# 401_FramePWR.net
KiCad netlist of a schematic drawn in Altium Designer
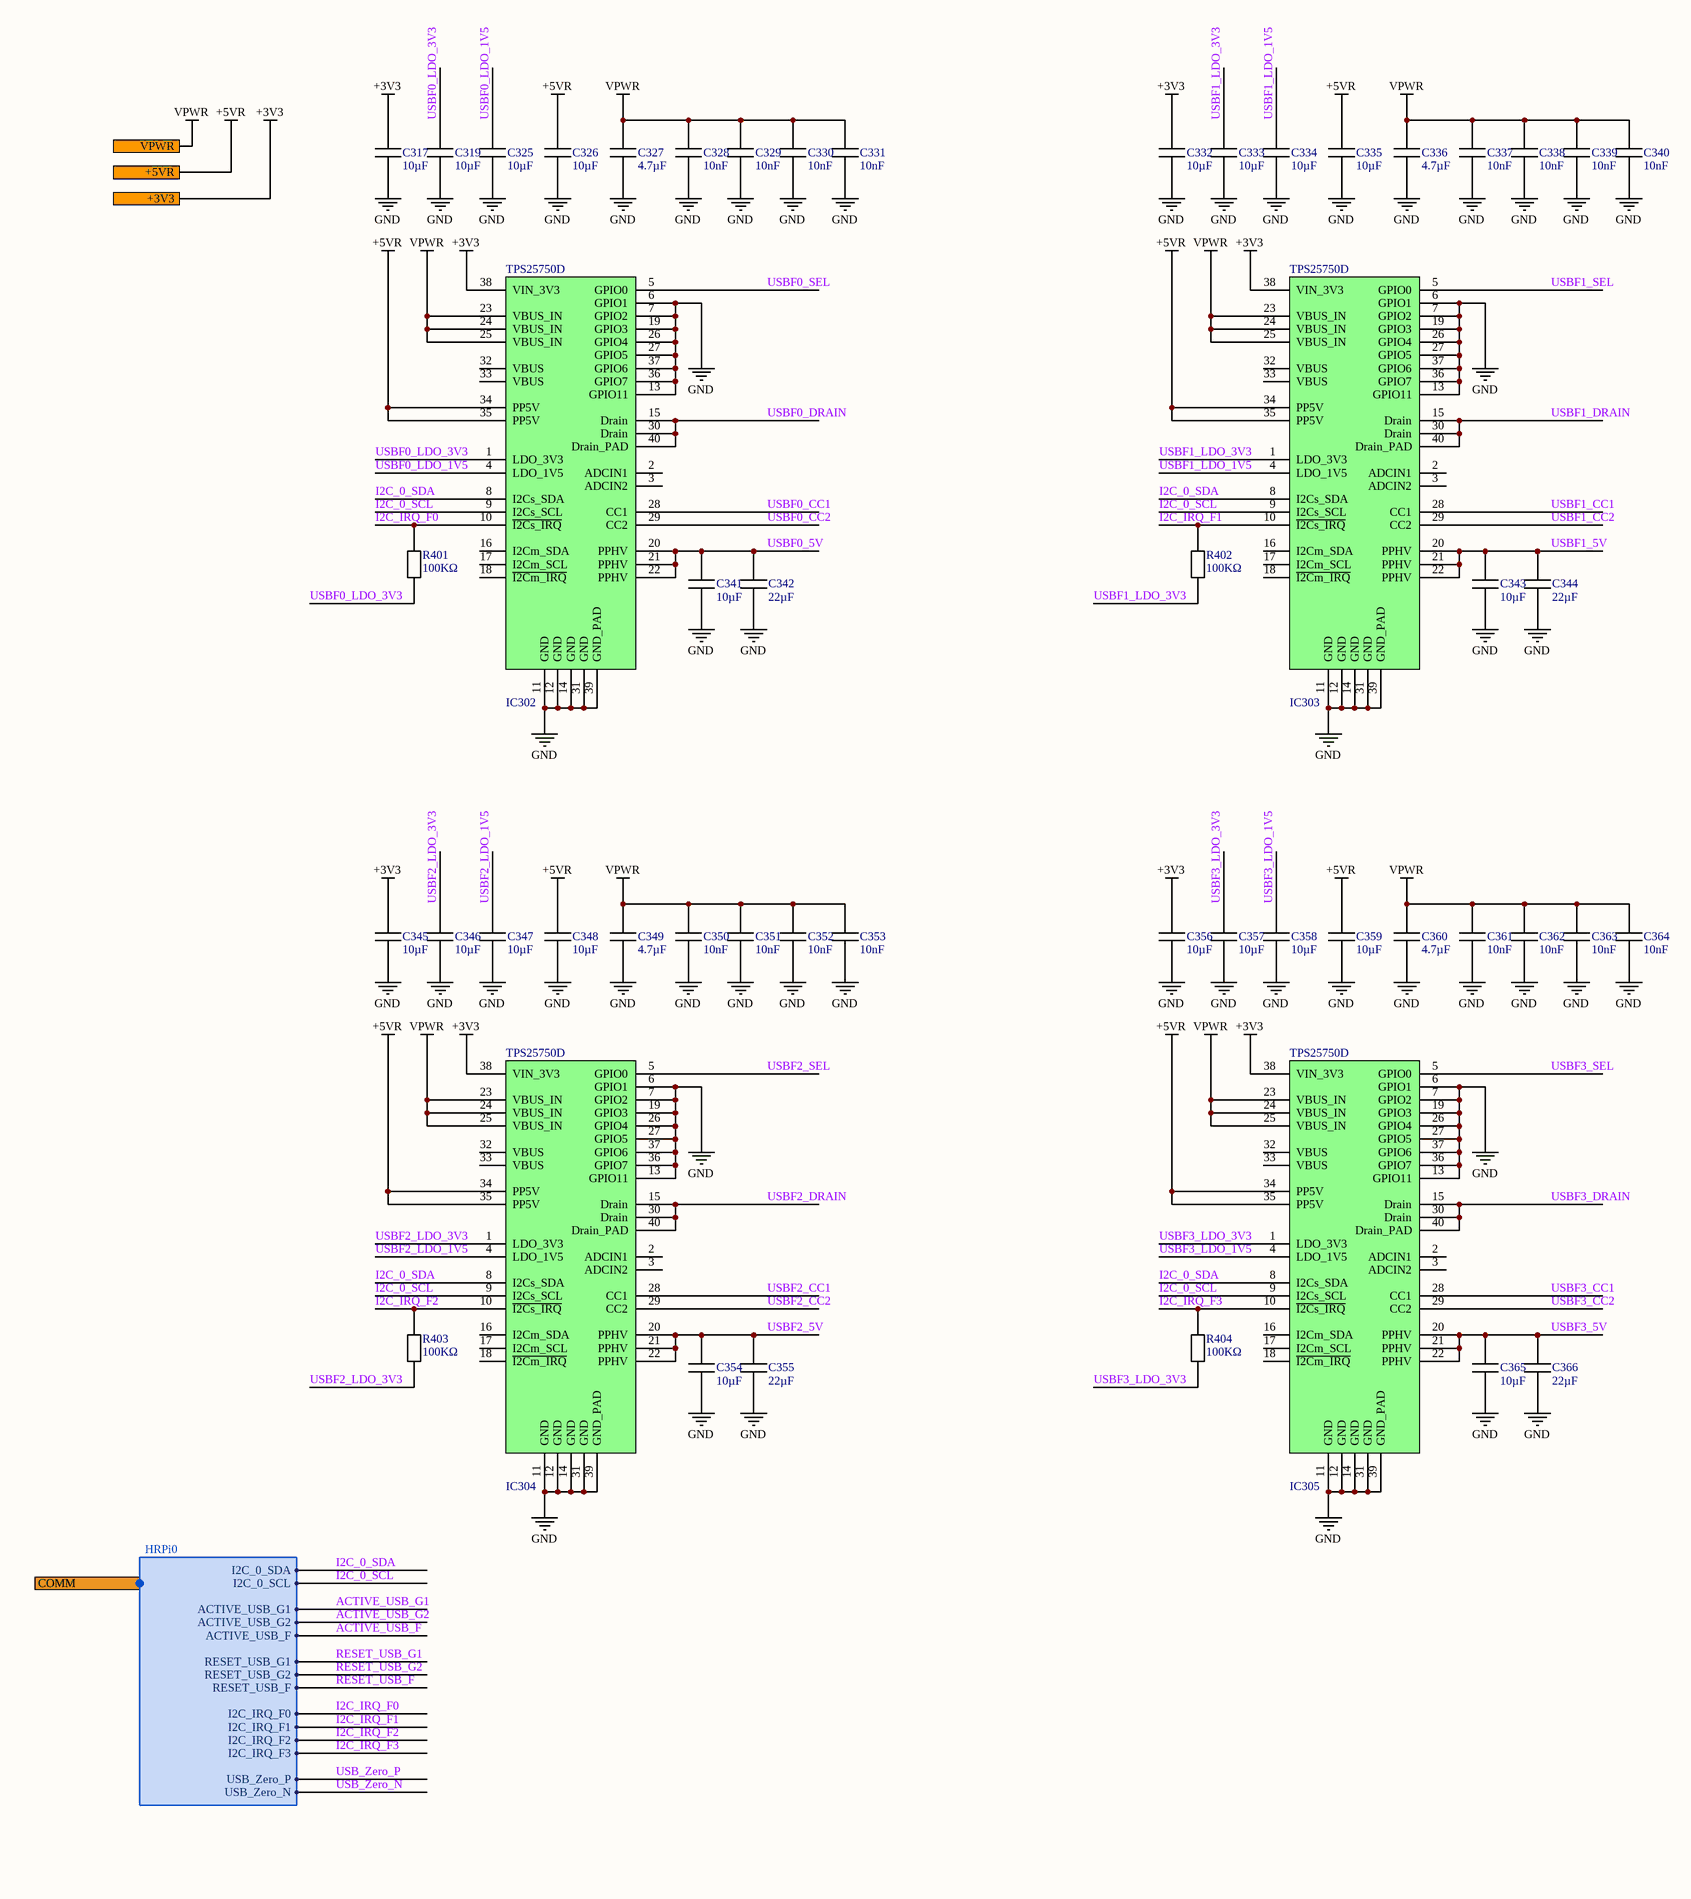
[diagram p0: 401_FramePWR.schdoc, left]
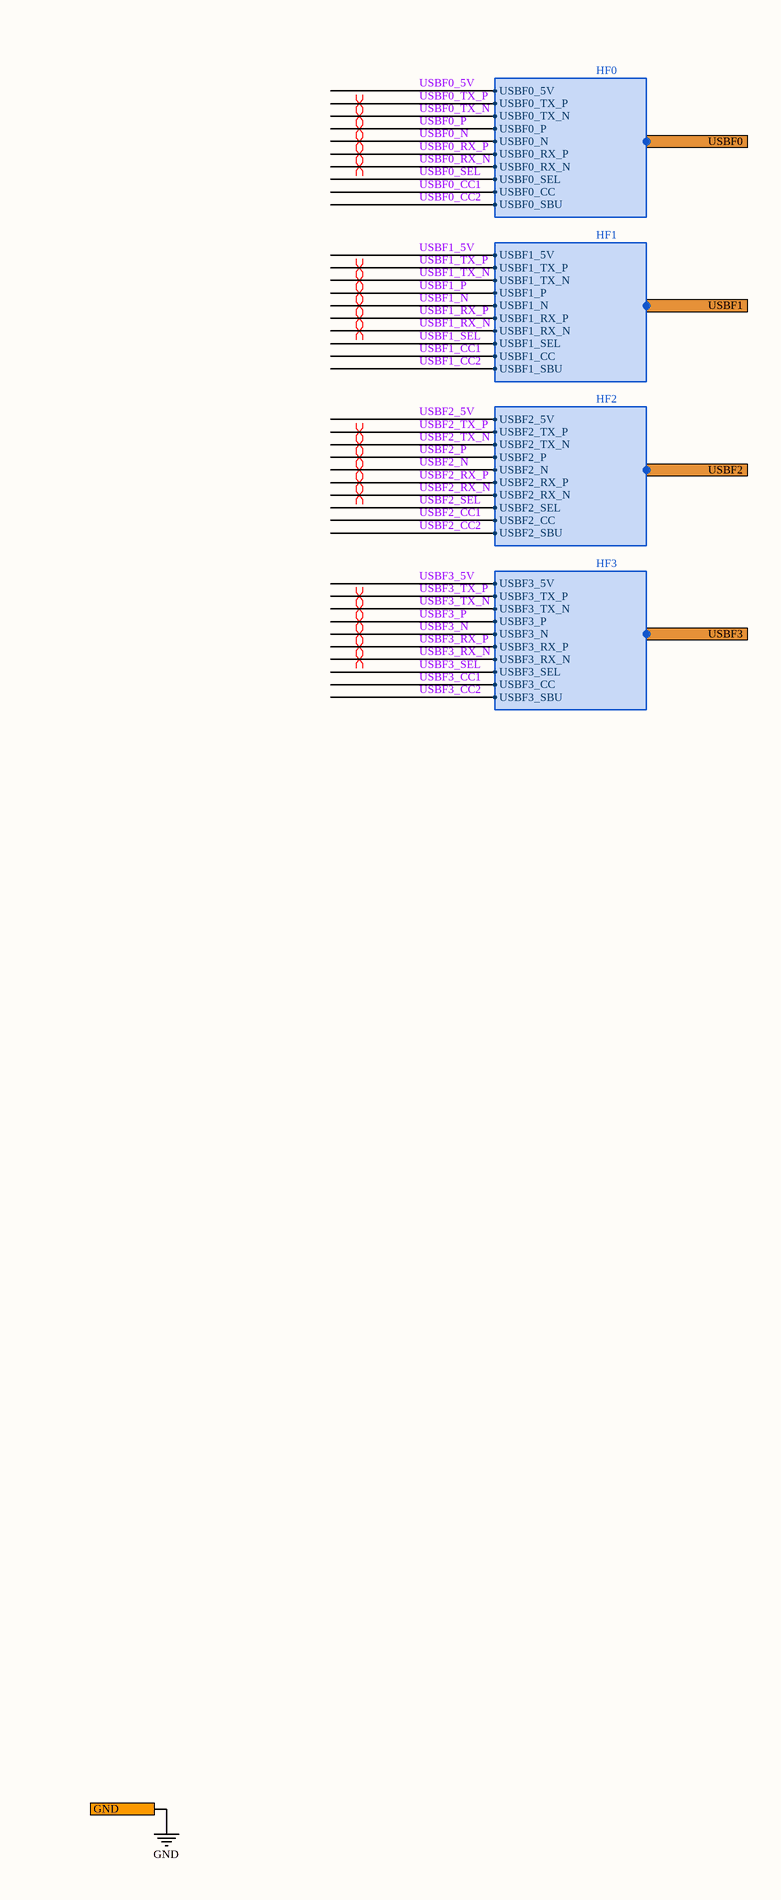
[diagram p1: 401_FramePWR.schdoc, right]

(export (version "E")
  (design (tool "Eeschema 10.0.6"))
  (components
    (comp (ref "C317")
      (value "10µF")
      (footprint "C0805")
      (description "10µF 16V 10% X5R")
      (fields
        (field (name "REFVAL") "10µF")
        (field (name "PART NUMBER") "CA0001")
        (field (name "MANFACTPART") "GRM21BR61C106KE15L")
      )
      (libsource (lib "GTS_Database") (part "C"))
    )
    (comp (ref "C319")
      (value "10µF")
      (footprint "C0805")
      (description "10µF 16V 10% X5R")
      (fields
        (field (name "REFVAL") "10µF")
        (field (name "PART NUMBER") "CA0001")
        (field (name "MANFACTPART") "GRM21BR61C106KE15L")
      )
      (libsource (lib "GTS_Database") (part "C"))
    )
    (comp (ref "C325")
      (value "10µF")
      (footprint "C0805")
      (description "10µF 16V 10% X5R")
      (fields
        (field (name "REFVAL") "10µF")
        (field (name "PART NUMBER") "CA0001")
        (field (name "MANFACTPART") "GRM21BR61C106KE15L")
      )
      (libsource (lib "GTS_Database") (part "C"))
    )
    (comp (ref "C326")
      (value "10µF")
      (footprint "C0805")
      (description "10µF 16V 10% X5R")
      (fields
        (field (name "REFVAL") "10µF")
        (field (name "PART NUMBER") "CA0001")
        (field (name "MANFACTPART") "GRM21BR61C106KE15L")
      )
      (libsource (lib "GTS_Database") (part "C"))
    )
    (comp (ref "C327")
      (value "4.7µF")
      (footprint "C1210")
      (description "4.7µF 100V 10% X5R")
      (fields
        (field (name "REFVAL") "4.7µF")
        (field (name "PART NUMBER") "CA0038")
        (field (name "MANFACTPART") "HMK325BJ475KM-PE")
      )
      (libsource (lib "GTS_Database") (part "C"))
    )
    (comp (ref "C328")
      (value "10nF")
      (footprint "C0805")
      (description "10nF 50V 10% X7R")
      (fields
        (field (name "REFVAL") "10nF")
        (field (name "PART NUMBER") "CA0021")
        (field (name "MANFACTPART") "C0805C103K5RAC")
      )
      (libsource (lib "GTS_Database") (part "C"))
    )
    (comp (ref "C329")
      (value "10nF")
      (footprint "C0805")
      (description "10nF 50V 10% X7R")
      (fields
        (field (name "REFVAL") "10nF")
        (field (name "PART NUMBER") "CA0021")
        (field (name "MANFACTPART") "C0805C103K5RAC")
      )
      (libsource (lib "GTS_Database") (part "C"))
    )
    (comp (ref "C330")
      (value "10nF")
      (footprint "C0805")
      (description "10nF 50V 10% X7R")
      (fields
        (field (name "REFVAL") "10nF")
        (field (name "PART NUMBER") "CA0021")
        (field (name "MANFACTPART") "C0805C103K5RAC")
      )
      (libsource (lib "GTS_Database") (part "C"))
    )
    (comp (ref "C331")
      (value "10nF")
      (footprint "C0805")
      (description "10nF 50V 10% X7R")
      (fields
        (field (name "REFVAL") "10nF")
        (field (name "PART NUMBER") "CA0021")
        (field (name "MANFACTPART") "C0805C103K5RAC")
      )
      (libsource (lib "GTS_Database") (part "C"))
    )
    (comp (ref "C332")
      (value "10µF")
      (footprint "C0805")
      (description "10µF 16V 10% X5R")
      (fields
        (field (name "REFVAL") "10µF")
        (field (name "PART NUMBER") "CA0001")
        (field (name "MANFACTPART") "GRM21BR61C106KE15L")
      )
      (libsource (lib "GTS_Database") (part "C"))
    )
    (comp (ref "C333")
      (value "10µF")
      (footprint "C0805")
      (description "10µF 16V 10% X5R")
      (fields
        (field (name "REFVAL") "10µF")
        (field (name "PART NUMBER") "CA0001")
        (field (name "MANFACTPART") "GRM21BR61C106KE15L")
      )
      (libsource (lib "GTS_Database") (part "C"))
    )
    (comp (ref "C334")
      (value "10µF")
      (footprint "C0805")
      (description "10µF 16V 10% X5R")
      (fields
        (field (name "REFVAL") "10µF")
        (field (name "PART NUMBER") "CA0001")
        (field (name "MANFACTPART") "GRM21BR61C106KE15L")
      )
      (libsource (lib "GTS_Database") (part "C"))
    )
    (comp (ref "C335")
      (value "10µF")
      (footprint "C0805")
      (description "10µF 16V 10% X5R")
      (fields
        (field (name "REFVAL") "10µF")
        (field (name "PART NUMBER") "CA0001")
        (field (name "MANFACTPART") "GRM21BR61C106KE15L")
      )
      (libsource (lib "GTS_Database") (part "C"))
    )
    (comp (ref "C336")
      (value "4.7µF")
      (footprint "C1210")
      (description "4.7µF 100V 10% X5R")
      (fields
        (field (name "REFVAL") "4.7µF")
        (field (name "PART NUMBER") "CA0038")
        (field (name "MANFACTPART") "HMK325BJ475KM-PE")
      )
      (libsource (lib "GTS_Database") (part "C"))
    )
    (comp (ref "C337")
      (value "10nF")
      (footprint "C0805")
      (description "10nF 50V 10% X7R")
      (fields
        (field (name "REFVAL") "10nF")
        (field (name "PART NUMBER") "CA0021")
        (field (name "MANFACTPART") "C0805C103K5RAC")
      )
      (libsource (lib "GTS_Database") (part "C"))
    )
    (comp (ref "C338")
      (value "10nF")
      (footprint "C0805")
      (description "10nF 50V 10% X7R")
      (fields
        (field (name "REFVAL") "10nF")
        (field (name "PART NUMBER") "CA0021")
        (field (name "MANFACTPART") "C0805C103K5RAC")
      )
      (libsource (lib "GTS_Database") (part "C"))
    )
    (comp (ref "C339")
      (value "10nF")
      (footprint "C0805")
      (description "10nF 50V 10% X7R")
      (fields
        (field (name "REFVAL") "10nF")
        (field (name "PART NUMBER") "CA0021")
        (field (name "MANFACTPART") "C0805C103K5RAC")
      )
      (libsource (lib "GTS_Database") (part "C"))
    )
    (comp (ref "C340")
      (value "10nF")
      (footprint "C0805")
      (description "10nF 50V 10% X7R")
      (fields
        (field (name "REFVAL") "10nF")
        (field (name "PART NUMBER") "CA0021")
        (field (name "MANFACTPART") "C0805C103K5RAC")
      )
      (libsource (lib "GTS_Database") (part "C"))
    )
    (comp (ref "C341")
      (value "10µF")
      (footprint "C1210")
      (description "10µF 63V 10% X7R")
      (fields
        (field (name "REFVAL") "10µF")
        (field (name "PART NUMBER") "CA0039")
        (field (name "MANFACTPART") "CL32B106KMVNNWE")
      )
      (libsource (lib "GTS_Database") (part "C"))
    )
    (comp (ref "C342")
      (value "22µF")
      (footprint "C2220")
      (description "22µF 63V 20% X7R")
      (fields
        (field (name "REFVAL") "22µF")
        (field (name "PART NUMBER") "CA0051")
        (field (name "MANFACTPART") "KRM55WR71J226MH01K")
      )
      (libsource (lib "GTS_Database") (part "C"))
    )
    (comp (ref "C343")
      (value "10µF")
      (footprint "C1210")
      (description "10µF 63V 10% X7R")
      (fields
        (field (name "REFVAL") "10µF")
        (field (name "PART NUMBER") "CA0039")
        (field (name "MANFACTPART") "CL32B106KMVNNWE")
      )
      (libsource (lib "GTS_Database") (part "C"))
    )
    (comp (ref "C344")
      (value "22µF")
      (footprint "C2220")
      (description "22µF 63V 20% X7R")
      (fields
        (field (name "REFVAL") "22µF")
        (field (name "PART NUMBER") "CA0051")
        (field (name "MANFACTPART") "KRM55WR71J226MH01K")
      )
      (libsource (lib "GTS_Database") (part "C"))
    )
    (comp (ref "C345")
      (value "10µF")
      (footprint "C0805")
      (description "10µF 16V 10% X5R")
      (fields
        (field (name "REFVAL") "10µF")
        (field (name "PART NUMBER") "CA0001")
        (field (name "MANFACTPART") "GRM21BR61C106KE15L")
      )
      (libsource (lib "GTS_Database") (part "C"))
    )
    (comp (ref "C346")
      (value "10µF")
      (footprint "C0805")
      (description "10µF 16V 10% X5R")
      (fields
        (field (name "REFVAL") "10µF")
        (field (name "PART NUMBER") "CA0001")
        (field (name "MANFACTPART") "GRM21BR61C106KE15L")
      )
      (libsource (lib "GTS_Database") (part "C"))
    )
    (comp (ref "C347")
      (value "10µF")
      (footprint "C0805")
      (description "10µF 16V 10% X5R")
      (fields
        (field (name "REFVAL") "10µF")
        (field (name "PART NUMBER") "CA0001")
        (field (name "MANFACTPART") "GRM21BR61C106KE15L")
      )
      (libsource (lib "GTS_Database") (part "C"))
    )
    (comp (ref "C348")
      (value "10µF")
      (footprint "C0805")
      (description "10µF 16V 10% X5R")
      (fields
        (field (name "REFVAL") "10µF")
        (field (name "PART NUMBER") "CA0001")
        (field (name "MANFACTPART") "GRM21BR61C106KE15L")
      )
      (libsource (lib "GTS_Database") (part "C"))
    )
    (comp (ref "C349")
      (value "4.7µF")
      (footprint "C1210")
      (description "4.7µF 100V 10% X5R")
      (fields
        (field (name "REFVAL") "4.7µF")
        (field (name "PART NUMBER") "CA0038")
        (field (name "MANFACTPART") "HMK325BJ475KM-PE")
      )
      (libsource (lib "GTS_Database") (part "C"))
    )
    (comp (ref "C350")
      (value "10nF")
      (footprint "C0805")
      (description "10nF 50V 10% X7R")
      (fields
        (field (name "REFVAL") "10nF")
        (field (name "PART NUMBER") "CA0021")
        (field (name "MANFACTPART") "C0805C103K5RAC")
      )
      (libsource (lib "GTS_Database") (part "C"))
    )
    (comp (ref "C351")
      (value "10nF")
      (footprint "C0805")
      (description "10nF 50V 10% X7R")
      (fields
        (field (name "REFVAL") "10nF")
        (field (name "PART NUMBER") "CA0021")
        (field (name "MANFACTPART") "C0805C103K5RAC")
      )
      (libsource (lib "GTS_Database") (part "C"))
    )
    (comp (ref "C352")
      (value "10nF")
      (footprint "C0805")
      (description "10nF 50V 10% X7R")
      (fields
        (field (name "REFVAL") "10nF")
        (field (name "PART NUMBER") "CA0021")
        (field (name "MANFACTPART") "C0805C103K5RAC")
      )
      (libsource (lib "GTS_Database") (part "C"))
    )
    (comp (ref "C353")
      (value "10nF")
      (footprint "C0805")
      (description "10nF 50V 10% X7R")
      (fields
        (field (name "REFVAL") "10nF")
        (field (name "PART NUMBER") "CA0021")
        (field (name "MANFACTPART") "C0805C103K5RAC")
      )
      (libsource (lib "GTS_Database") (part "C"))
    )
    (comp (ref "C354")
      (value "10µF")
      (footprint "C1210")
      (description "10µF 63V 10% X7R")
      (fields
        (field (name "REFVAL") "10µF")
        (field (name "PART NUMBER") "CA0039")
        (field (name "MANFACTPART") "CL32B106KMVNNWE")
      )
      (libsource (lib "GTS_Database") (part "C"))
    )
    (comp (ref "C355")
      (value "22µF")
      (footprint "C2220")
      (description "22µF 63V 20% X7R")
      (fields
        (field (name "REFVAL") "22µF")
        (field (name "PART NUMBER") "CA0051")
        (field (name "MANFACTPART") "KRM55WR71J226MH01K")
      )
      (libsource (lib "GTS_Database") (part "C"))
    )
    (comp (ref "C356")
      (value "10µF")
      (footprint "C0805")
      (description "10µF 16V 10% X5R")
      (fields
        (field (name "REFVAL") "10µF")
        (field (name "PART NUMBER") "CA0001")
        (field (name "MANFACTPART") "GRM21BR61C106KE15L")
      )
      (libsource (lib "GTS_Database") (part "C"))
    )
    (comp (ref "C357")
      (value "10µF")
      (footprint "C0805")
      (description "10µF 16V 10% X5R")
      (fields
        (field (name "REFVAL") "10µF")
        (field (name "PART NUMBER") "CA0001")
        (field (name "MANFACTPART") "GRM21BR61C106KE15L")
      )
      (libsource (lib "GTS_Database") (part "C"))
    )
    (comp (ref "C358")
      (value "10µF")
      (footprint "C0805")
      (description "10µF 16V 10% X5R")
      (fields
        (field (name "REFVAL") "10µF")
        (field (name "PART NUMBER") "CA0001")
        (field (name "MANFACTPART") "GRM21BR61C106KE15L")
      )
      (libsource (lib "GTS_Database") (part "C"))
    )
    (comp (ref "C359")
      (value "10µF")
      (footprint "C0805")
      (description "10µF 16V 10% X5R")
      (fields
        (field (name "REFVAL") "10µF")
        (field (name "PART NUMBER") "CA0001")
        (field (name "MANFACTPART") "GRM21BR61C106KE15L")
      )
      (libsource (lib "GTS_Database") (part "C"))
    )
    (comp (ref "C360")
      (value "4.7µF")
      (footprint "C1210")
      (description "4.7µF 100V 10% X5R")
      (fields
        (field (name "REFVAL") "4.7µF")
        (field (name "PART NUMBER") "CA0038")
        (field (name "MANFACTPART") "HMK325BJ475KM-PE")
      )
      (libsource (lib "GTS_Database") (part "C"))
    )
    (comp (ref "C361")
      (value "10nF")
      (footprint "C0805")
      (description "10nF 50V 10% X7R")
      (fields
        (field (name "REFVAL") "10nF")
        (field (name "PART NUMBER") "CA0021")
        (field (name "MANFACTPART") "C0805C103K5RAC")
      )
      (libsource (lib "GTS_Database") (part "C"))
    )
    (comp (ref "C362")
      (value "10nF")
      (footprint "C0805")
      (description "10nF 50V 10% X7R")
      (fields
        (field (name "REFVAL") "10nF")
        (field (name "PART NUMBER") "CA0021")
        (field (name "MANFACTPART") "C0805C103K5RAC")
      )
      (libsource (lib "GTS_Database") (part "C"))
    )
    (comp (ref "C363")
      (value "10nF")
      (footprint "C0805")
      (description "10nF 50V 10% X7R")
      (fields
        (field (name "REFVAL") "10nF")
        (field (name "PART NUMBER") "CA0021")
        (field (name "MANFACTPART") "C0805C103K5RAC")
      )
      (libsource (lib "GTS_Database") (part "C"))
    )
    (comp (ref "C364")
      (value "10nF")
      (footprint "C0805")
      (description "10nF 50V 10% X7R")
      (fields
        (field (name "REFVAL") "10nF")
        (field (name "PART NUMBER") "CA0021")
        (field (name "MANFACTPART") "C0805C103K5RAC")
      )
      (libsource (lib "GTS_Database") (part "C"))
    )
    (comp (ref "C365")
      (value "10µF")
      (footprint "C1210")
      (description "10µF 63V 10% X7R")
      (fields
        (field (name "REFVAL") "10µF")
        (field (name "PART NUMBER") "CA0039")
        (field (name "MANFACTPART") "CL32B106KMVNNWE")
      )
      (libsource (lib "GTS_Database") (part "C"))
    )
    (comp (ref "C366")
      (value "22µF")
      (footprint "C2220")
      (description "22µF 63V 20% X7R")
      (fields
        (field (name "REFVAL") "22µF")
        (field (name "PART NUMBER") "CA0051")
        (field (name "MANFACTPART") "KRM55WR71J226MH01K")
      )
      (libsource (lib "GTS_Database") (part "C"))
    )
    (comp (ref "IC302")
      (value "TPS25750D")
      (footprint "QFNRJK-38")
      (description "USB Type-C and USB PD Controller with Integrated Power Switches Optimized for Power Applications")
      (fields (field (name "REFVAL") "TPS25750D") (field (name "PART NUMBER") "IC0041"))
      (libsource (lib "GTS_Database") (part "TPS25750D"))
    )
    (comp (ref "IC303")
      (value "TPS25750D")
      (footprint "QFNRJK-38")
      (description "USB Type-C and USB PD Controller with Integrated Power Switches Optimized for Power Applications")
      (fields (field (name "REFVAL") "TPS25750D") (field (name "PART NUMBER") "IC0041"))
      (libsource (lib "GTS_Database") (part "TPS25750D"))
    )
    (comp (ref "IC304")
      (value "TPS25750D")
      (footprint "QFNRJK-38")
      (description "USB Type-C and USB PD Controller with Integrated Power Switches Optimized for Power Applications")
      (fields (field (name "REFVAL") "TPS25750D") (field (name "PART NUMBER") "IC0041"))
      (libsource (lib "GTS_Database") (part "TPS25750D"))
    )
    (comp (ref "IC305")
      (value "TPS25750D")
      (footprint "QFNRJK-38")
      (description "USB Type-C and USB PD Controller with Integrated Power Switches Optimized for Power Applications")
      (fields (field (name "REFVAL") "TPS25750D") (field (name "PART NUMBER") "IC0041"))
      (libsource (lib "GTS_Database") (part "TPS25750D"))
    )
    (comp (ref "R401")
      (value "100KΩ")
      (footprint "R0402")
      (description "100KΩ 1% 62.5mW 100PPM")
      (fields
        (field (name "REFVAL") "100KΩ")
        (field (name "PART NUMBER") "RS0036")
        (field (name "MANFACTPART") "AC0402FR-13100KL")
      )
      (libsource (lib "GTS_Database") (part "R"))
    )
    (comp (ref "R402")
      (value "100KΩ")
      (footprint "R0402")
      (description "100KΩ 1% 62.5mW 100PPM")
      (fields
        (field (name "REFVAL") "100KΩ")
        (field (name "PART NUMBER") "RS0036")
        (field (name "MANFACTPART") "AC0402FR-13100KL")
      )
      (libsource (lib "GTS_Database") (part "R"))
    )
    (comp (ref "R403")
      (value "100KΩ")
      (footprint "R0402")
      (description "100KΩ 1% 62.5mW 100PPM")
      (fields
        (field (name "REFVAL") "100KΩ")
        (field (name "PART NUMBER") "RS0036")
        (field (name "MANFACTPART") "AC0402FR-13100KL")
      )
      (libsource (lib "GTS_Database") (part "R"))
    )
    (comp (ref "R404")
      (value "100KΩ")
      (footprint "R0402")
      (description "100KΩ 1% 62.5mW 100PPM")
      (fields
        (field (name "REFVAL") "100KΩ")
        (field (name "PART NUMBER") "RS0036")
        (field (name "MANFACTPART") "AC0402FR-13100KL")
      )
      (libsource (lib "GTS_Database") (part "R"))
    )
  )
  (nets
    (net (code "6") (name "+3V3") (class "Default")
      (node (ref "C317") (pin "1") (pinfunction "1_1") (pintype "passive"))
      (node (ref "C332") (pin "1") (pinfunction "1_1") (pintype "passive"))
      (node (ref "C345") (pin "1") (pinfunction "1_1") (pintype "passive"))
      (node (ref "C356") (pin "1") (pinfunction "1_1") (pintype "passive"))
      (node (ref "IC302") (pin "38") (pinfunction "VIN_3V3_38") (pintype "passive"))
      (node (ref "IC303") (pin "38") (pinfunction "VIN_3V3_38") (pintype "passive"))
      (node (ref "IC304") (pin "38") (pinfunction "VIN_3V3_38") (pintype "passive"))
      (node (ref "IC305") (pin "38") (pinfunction "VIN_3V3_38") (pintype "passive"))
    )
    (net (code "7") (name "+5VR") (class "Default")
      (node (ref "C326") (pin "1") (pinfunction "1_1") (pintype "passive"))
      (node (ref "C335") (pin "1") (pinfunction "1_1") (pintype "passive"))
      (node (ref "C348") (pin "1") (pinfunction "1_1") (pintype "passive"))
      (node (ref "C359") (pin "1") (pinfunction "1_1") (pintype "passive"))
      (node (ref "IC302") (pin "34") (pinfunction "PP5V_34") (pintype "passive"))
      (node (ref "IC302") (pin "35") (pinfunction "PP5V_35") (pintype "passive"))
      (node (ref "IC303") (pin "34") (pinfunction "PP5V_34") (pintype "passive"))
      (node (ref "IC303") (pin "35") (pinfunction "PP5V_35") (pintype "passive"))
      (node (ref "IC304") (pin "34") (pinfunction "PP5V_34") (pintype "passive"))
      (node (ref "IC304") (pin "35") (pinfunction "PP5V_35") (pintype "passive"))
      (node (ref "IC305") (pin "34") (pinfunction "PP5V_34") (pintype "passive"))
      (node (ref "IC305") (pin "35") (pinfunction "PP5V_35") (pintype "passive"))
    )
    (net (code "11") (name "/I2C_0_SCL") (class "Default")
      (node (ref "IC302") (pin "9") (pinfunction "I2Cs_SCL_9") (pintype "passive"))
      (node (ref "IC303") (pin "9") (pinfunction "I2Cs_SCL_9") (pintype "passive"))
      (node (ref "IC304") (pin "9") (pinfunction "I2Cs_SCL_9") (pintype "passive"))
      (node (ref "IC305") (pin "9") (pinfunction "I2Cs_SCL_9") (pintype "passive"))
    )
    (net (code "12") (name "/I2C_0_SDA") (class "Default")
      (node (ref "IC302") (pin "8") (pinfunction "I2Cs_SDA_8") (pintype "passive"))
      (node (ref "IC303") (pin "8") (pinfunction "I2Cs_SDA_8") (pintype "passive"))
      (node (ref "IC304") (pin "8") (pinfunction "I2Cs_SDA_8") (pintype "passive"))
      (node (ref "IC305") (pin "8") (pinfunction "I2Cs_SDA_8") (pintype "passive"))
    )
    (net (code "13") (name "/I2C_IRQ_F0") (class "Default")
      (node (ref "IC302") (pin "10") (pinfunction "I2Cs_IRQ_10") (pintype "passive"))
      (node (ref "R401") (pin "2") (pinfunction "2_2") (pintype "passive"))
    )
    (net (code "14") (name "/I2C_IRQ_F1") (class "Default")
      (node (ref "IC303") (pin "10") (pinfunction "I2Cs_IRQ_10") (pintype "passive"))
      (node (ref "R402") (pin "2") (pinfunction "2_2") (pintype "passive"))
    )
    (net (code "15") (name "/I2C_IRQ_F2") (class "Default")
      (node (ref "IC304") (pin "10") (pinfunction "I2Cs_IRQ_10") (pintype "passive"))
      (node (ref "R403") (pin "2") (pinfunction "2_2") (pintype "passive"))
    )
    (net (code "16") (name "/I2C_IRQ_F3") (class "Default")
      (node (ref "IC305") (pin "10") (pinfunction "I2Cs_IRQ_10") (pintype "passive"))
      (node (ref "R404") (pin "2") (pinfunction "2_2") (pintype "passive"))
    )
    (net (code "20") (name "/USBF0_5V") (class "Default")
      (node (ref "C341") (pin "1") (pinfunction "1_1") (pintype "passive"))
      (node (ref "C342") (pin "1") (pinfunction "1_1") (pintype "passive"))
      (node (ref "IC302") (pin "20") (pinfunction "PPHV_20") (pintype "passive"))
      (node (ref "IC302") (pin "21") (pinfunction "PPHV_21") (pintype "passive"))
      (node (ref "IC302") (pin "22") (pinfunction "PPHV_22") (pintype "passive"))
    )
    (net (code "21") (name "/USBF0_CC1") (class "Default")
      (node (ref "IC302") (pin "28") (pinfunction "CC1_28") (pintype "passive"))
    )
    (net (code "22") (name "/USBF0_CC2") (class "Default")
      (node (ref "IC302") (pin "29") (pinfunction "CC2_29") (pintype "passive"))
    )
    (net (code "23") (name "/USBF0_DRAIN") (class "Default")
      (node (ref "IC302") (pin "15") (pinfunction "Drain_15") (pintype "passive"))
      (node (ref "IC302") (pin "30") (pinfunction "Drain_30") (pintype "passive"))
      (node (ref "IC302") (pin "40") (pinfunction "Drain_PAD_40") (pintype "passive"))
    )
    (net (code "24") (name "/USBF0_LDO_1V5") (class "Default")
      (node (ref "C325") (pin "1") (pinfunction "1_1") (pintype "passive"))
      (node (ref "IC302") (pin "4") (pinfunction "LDO_1V5_4") (pintype "passive"))
    )
    (net (code "25") (name "/USBF0_LDO_3V3") (class "Default")
      (node (ref "C319") (pin "1") (pinfunction "1_1") (pintype "passive"))
      (node (ref "IC302") (pin "1") (pinfunction "LDO_3V3_1") (pintype "passive"))
      (node (ref "R401") (pin "1") (pinfunction "1_1") (pintype "passive"))
    )
    (net (code "30") (name "/USBF0_SEL") (class "Default")
      (node (ref "IC302") (pin "5") (pinfunction "GPIO0_5") (pintype "passive"))
    )
    (net (code "33") (name "/USBF1_5V") (class "Default")
      (node (ref "C343") (pin "1") (pinfunction "1_1") (pintype "passive"))
      (node (ref "C344") (pin "1") (pinfunction "1_1") (pintype "passive"))
      (node (ref "IC303") (pin "20") (pinfunction "PPHV_20") (pintype "passive"))
      (node (ref "IC303") (pin "21") (pinfunction "PPHV_21") (pintype "passive"))
      (node (ref "IC303") (pin "22") (pinfunction "PPHV_22") (pintype "passive"))
    )
    (net (code "34") (name "/USBF1_CC1") (class "Default")
      (node (ref "IC303") (pin "28") (pinfunction "CC1_28") (pintype "passive"))
    )
    (net (code "35") (name "/USBF1_CC2") (class "Default")
      (node (ref "IC303") (pin "29") (pinfunction "CC2_29") (pintype "passive"))
    )
    (net (code "36") (name "/USBF1_DRAIN") (class "Default")
      (node (ref "IC303") (pin "15") (pinfunction "Drain_15") (pintype "passive"))
      (node (ref "IC303") (pin "30") (pinfunction "Drain_30") (pintype "passive"))
      (node (ref "IC303") (pin "40") (pinfunction "Drain_PAD_40") (pintype "passive"))
    )
    (net (code "37") (name "/USBF1_LDO_1V5") (class "Default")
      (node (ref "C334") (pin "1") (pinfunction "1_1") (pintype "passive"))
      (node (ref "IC303") (pin "4") (pinfunction "LDO_1V5_4") (pintype "passive"))
    )
    (net (code "38") (name "/USBF1_LDO_3V3") (class "Default")
      (node (ref "C333") (pin "1") (pinfunction "1_1") (pintype "passive"))
      (node (ref "IC303") (pin "1") (pinfunction "LDO_3V3_1") (pintype "passive"))
      (node (ref "R402") (pin "1") (pinfunction "1_1") (pintype "passive"))
    )
    (net (code "43") (name "/USBF1_SEL") (class "Default")
      (node (ref "IC303") (pin "5") (pinfunction "GPIO0_5") (pintype "passive"))
    )
    (net (code "46") (name "/USBF2_5V") (class "Default")
      (node (ref "C354") (pin "1") (pinfunction "1_1") (pintype "passive"))
      (node (ref "C355") (pin "1") (pinfunction "1_1") (pintype "passive"))
      (node (ref "IC304") (pin "20") (pinfunction "PPHV_20") (pintype "passive"))
      (node (ref "IC304") (pin "21") (pinfunction "PPHV_21") (pintype "passive"))
      (node (ref "IC304") (pin "22") (pinfunction "PPHV_22") (pintype "passive"))
    )
    (net (code "47") (name "/USBF2_CC1") (class "Default")
      (node (ref "IC304") (pin "28") (pinfunction "CC1_28") (pintype "passive"))
    )
    (net (code "48") (name "/USBF2_CC2") (class "Default")
      (node (ref "IC304") (pin "29") (pinfunction "CC2_29") (pintype "passive"))
    )
    (net (code "49") (name "/USBF2_DRAIN") (class "Default")
      (node (ref "IC304") (pin "15") (pinfunction "Drain_15") (pintype "passive"))
      (node (ref "IC304") (pin "30") (pinfunction "Drain_30") (pintype "passive"))
      (node (ref "IC304") (pin "40") (pinfunction "Drain_PAD_40") (pintype "passive"))
    )
    (net (code "50") (name "/USBF2_LDO_1V5") (class "Default")
      (node (ref "C347") (pin "1") (pinfunction "1_1") (pintype "passive"))
      (node (ref "IC304") (pin "4") (pinfunction "LDO_1V5_4") (pintype "passive"))
    )
    (net (code "51") (name "/USBF2_LDO_3V3") (class "Default")
      (node (ref "C346") (pin "1") (pinfunction "1_1") (pintype "passive"))
      (node (ref "IC304") (pin "1") (pinfunction "LDO_3V3_1") (pintype "passive"))
      (node (ref "R403") (pin "1") (pinfunction "1_1") (pintype "passive"))
    )
    (net (code "56") (name "/USBF2_SEL") (class "Default")
      (node (ref "IC304") (pin "5") (pinfunction "GPIO0_5") (pintype "passive"))
    )
    (net (code "59") (name "/USBF3_5V") (class "Default")
      (node (ref "C365") (pin "1") (pinfunction "1_1") (pintype "passive"))
      (node (ref "C366") (pin "1") (pinfunction "1_1") (pintype "passive"))
      (node (ref "IC305") (pin "20") (pinfunction "PPHV_20") (pintype "passive"))
      (node (ref "IC305") (pin "21") (pinfunction "PPHV_21") (pintype "passive"))
      (node (ref "IC305") (pin "22") (pinfunction "PPHV_22") (pintype "passive"))
    )
    (net (code "60") (name "/USBF3_CC1") (class "Default")
      (node (ref "IC305") (pin "28") (pinfunction "CC1_28") (pintype "passive"))
    )
    (net (code "61") (name "/USBF3_CC2") (class "Default")
      (node (ref "IC305") (pin "29") (pinfunction "CC2_29") (pintype "passive"))
    )
    (net (code "62") (name "/USBF3_DRAIN") (class "Default")
      (node (ref "IC305") (pin "15") (pinfunction "Drain_15") (pintype "passive"))
      (node (ref "IC305") (pin "30") (pinfunction "Drain_30") (pintype "passive"))
      (node (ref "IC305") (pin "40") (pinfunction "Drain_PAD_40") (pintype "passive"))
    )
    (net (code "63") (name "/USBF3_LDO_1V5") (class "Default")
      (node (ref "C358") (pin "1") (pinfunction "1_1") (pintype "passive"))
      (node (ref "IC305") (pin "4") (pinfunction "LDO_1V5_4") (pintype "passive"))
    )
    (net (code "64") (name "/USBF3_LDO_3V3") (class "Default")
      (node (ref "C357") (pin "1") (pinfunction "1_1") (pintype "passive"))
      (node (ref "IC305") (pin "1") (pinfunction "LDO_3V3_1") (pintype "passive"))
      (node (ref "R404") (pin "1") (pinfunction "1_1") (pintype "passive"))
    )
    (net (code "69") (name "/USBF3_SEL") (class "Default")
      (node (ref "IC305") (pin "5") (pinfunction "GPIO0_5") (pintype "passive"))
    )
    (net (code "79") (name "GND") (class "Default")
      (node (ref "C317") (pin "2") (pinfunction "2_2") (pintype "passive"))
      (node (ref "C319") (pin "2") (pinfunction "2_2") (pintype "passive"))
      (node (ref "C325") (pin "2") (pinfunction "2_2") (pintype "passive"))
      (node (ref "C326") (pin "2") (pinfunction "2_2") (pintype "passive"))
      (node (ref "C327") (pin "2") (pinfunction "2_2") (pintype "passive"))
      (node (ref "C328") (pin "2") (pinfunction "2_2") (pintype "passive"))
      (node (ref "C329") (pin "2") (pinfunction "2_2") (pintype "passive"))
      (node (ref "C330") (pin "2") (pinfunction "2_2") (pintype "passive"))
      (node (ref "C331") (pin "2") (pinfunction "2_2") (pintype "passive"))
      (node (ref "C332") (pin "2") (pinfunction "2_2") (pintype "passive"))
      (node (ref "C333") (pin "2") (pinfunction "2_2") (pintype "passive"))
      (node (ref "C334") (pin "2") (pinfunction "2_2") (pintype "passive"))
      (node (ref "C335") (pin "2") (pinfunction "2_2") (pintype "passive"))
      (node (ref "C336") (pin "2") (pinfunction "2_2") (pintype "passive"))
      (node (ref "C337") (pin "2") (pinfunction "2_2") (pintype "passive"))
      (node (ref "C338") (pin "2") (pinfunction "2_2") (pintype "passive"))
      (node (ref "C339") (pin "2") (pinfunction "2_2") (pintype "passive"))
      (node (ref "C340") (pin "2") (pinfunction "2_2") (pintype "passive"))
      (node (ref "C341") (pin "2") (pinfunction "2_2") (pintype "passive"))
      (node (ref "C342") (pin "2") (pinfunction "2_2") (pintype "passive"))
      (node (ref "C343") (pin "2") (pinfunction "2_2") (pintype "passive"))
      (node (ref "C344") (pin "2") (pinfunction "2_2") (pintype "passive"))
      (node (ref "C345") (pin "2") (pinfunction "2_2") (pintype "passive"))
      (node (ref "C346") (pin "2") (pinfunction "2_2") (pintype "passive"))
      (node (ref "C347") (pin "2") (pinfunction "2_2") (pintype "passive"))
      (node (ref "C348") (pin "2") (pinfunction "2_2") (pintype "passive"))
      (node (ref "C349") (pin "2") (pinfunction "2_2") (pintype "passive"))
      (node (ref "C350") (pin "2") (pinfunction "2_2") (pintype "passive"))
      (node (ref "C351") (pin "2") (pinfunction "2_2") (pintype "passive"))
      (node (ref "C352") (pin "2") (pinfunction "2_2") (pintype "passive"))
      (node (ref "C353") (pin "2") (pinfunction "2_2") (pintype "passive"))
      (node (ref "C354") (pin "2") (pinfunction "2_2") (pintype "passive"))
      (node (ref "C355") (pin "2") (pinfunction "2_2") (pintype "passive"))
      (node (ref "C356") (pin "2") (pinfunction "2_2") (pintype "passive"))
      (node (ref "C357") (pin "2") (pinfunction "2_2") (pintype "passive"))
      (node (ref "C358") (pin "2") (pinfunction "2_2") (pintype "passive"))
      (node (ref "C359") (pin "2") (pinfunction "2_2") (pintype "passive"))
      (node (ref "C360") (pin "2") (pinfunction "2_2") (pintype "passive"))
      (node (ref "C361") (pin "2") (pinfunction "2_2") (pintype "passive"))
      (node (ref "C362") (pin "2") (pinfunction "2_2") (pintype "passive"))
      (node (ref "C363") (pin "2") (pinfunction "2_2") (pintype "passive"))
      (node (ref "C364") (pin "2") (pinfunction "2_2") (pintype "passive"))
      (node (ref "C365") (pin "2") (pinfunction "2_2") (pintype "passive"))
      (node (ref "C366") (pin "2") (pinfunction "2_2") (pintype "passive"))
      (node (ref "IC302") (pin "11") (pinfunction "GND_11") (pintype "passive"))
      (node (ref "IC302") (pin "12") (pinfunction "GND_12") (pintype "passive"))
      (node (ref "IC302") (pin "13") (pinfunction "GPIO11_13") (pintype "passive"))
      (node (ref "IC302") (pin "14") (pinfunction "GND_14") (pintype "passive"))
      (node (ref "IC302") (pin "19") (pinfunction "GPIO3_19") (pintype "passive"))
      (node (ref "IC302") (pin "26") (pinfunction "GPIO4_26") (pintype "passive"))
      (node (ref "IC302") (pin "27") (pinfunction "GPIO5_27") (pintype "passive"))
      (node (ref "IC302") (pin "31") (pinfunction "GND_31") (pintype "passive"))
      (node (ref "IC302") (pin "36") (pinfunction "GPIO7_36") (pintype "passive"))
      (node (ref "IC302") (pin "37") (pinfunction "GPIO6_37") (pintype "passive"))
      (node (ref "IC302") (pin "39") (pinfunction "GND_PAD_39") (pintype "passive"))
      (node (ref "IC302") (pin "6") (pinfunction "GPIO1_6") (pintype "passive"))
      (node (ref "IC302") (pin "7") (pinfunction "GPIO2_7") (pintype "passive"))
      (node (ref "IC303") (pin "11") (pinfunction "GND_11") (pintype "passive"))
      (node (ref "IC303") (pin "12") (pinfunction "GND_12") (pintype "passive"))
      (node (ref "IC303") (pin "13") (pinfunction "GPIO11_13") (pintype "passive"))
      (node (ref "IC303") (pin "14") (pinfunction "GND_14") (pintype "passive"))
      (node (ref "IC303") (pin "19") (pinfunction "GPIO3_19") (pintype "passive"))
      (node (ref "IC303") (pin "26") (pinfunction "GPIO4_26") (pintype "passive"))
      (node (ref "IC303") (pin "27") (pinfunction "GPIO5_27") (pintype "passive"))
      (node (ref "IC303") (pin "31") (pinfunction "GND_31") (pintype "passive"))
      (node (ref "IC303") (pin "36") (pinfunction "GPIO7_36") (pintype "passive"))
      (node (ref "IC303") (pin "37") (pinfunction "GPIO6_37") (pintype "passive"))
      (node (ref "IC303") (pin "39") (pinfunction "GND_PAD_39") (pintype "passive"))
      (node (ref "IC303") (pin "6") (pinfunction "GPIO1_6") (pintype "passive"))
      (node (ref "IC303") (pin "7") (pinfunction "GPIO2_7") (pintype "passive"))
      (node (ref "IC304") (pin "11") (pinfunction "GND_11") (pintype "passive"))
      (node (ref "IC304") (pin "12") (pinfunction "GND_12") (pintype "passive"))
      (node (ref "IC304") (pin "13") (pinfunction "GPIO11_13") (pintype "passive"))
      (node (ref "IC304") (pin "14") (pinfunction "GND_14") (pintype "passive"))
      (node (ref "IC304") (pin "19") (pinfunction "GPIO3_19") (pintype "passive"))
      (node (ref "IC304") (pin "26") (pinfunction "GPIO4_26") (pintype "passive"))
      (node (ref "IC304") (pin "27") (pinfunction "GPIO5_27") (pintype "passive"))
      (node (ref "IC304") (pin "31") (pinfunction "GND_31") (pintype "passive"))
      (node (ref "IC304") (pin "36") (pinfunction "GPIO7_36") (pintype "passive"))
      (node (ref "IC304") (pin "37") (pinfunction "GPIO6_37") (pintype "passive"))
      (node (ref "IC304") (pin "39") (pinfunction "GND_PAD_39") (pintype "passive"))
      (node (ref "IC304") (pin "6") (pinfunction "GPIO1_6") (pintype "passive"))
      (node (ref "IC304") (pin "7") (pinfunction "GPIO2_7") (pintype "passive"))
      (node (ref "IC305") (pin "11") (pinfunction "GND_11") (pintype "passive"))
      (node (ref "IC305") (pin "12") (pinfunction "GND_12") (pintype "passive"))
      (node (ref "IC305") (pin "13") (pinfunction "GPIO11_13") (pintype "passive"))
      (node (ref "IC305") (pin "14") (pinfunction "GND_14") (pintype "passive"))
      (node (ref "IC305") (pin "19") (pinfunction "GPIO3_19") (pintype "passive"))
      (node (ref "IC305") (pin "26") (pinfunction "GPIO4_26") (pintype "passive"))
      (node (ref "IC305") (pin "27") (pinfunction "GPIO5_27") (pintype "passive"))
      (node (ref "IC305") (pin "31") (pinfunction "GND_31") (pintype "passive"))
      (node (ref "IC305") (pin "36") (pinfunction "GPIO7_36") (pintype "passive"))
      (node (ref "IC305") (pin "37") (pinfunction "GPIO6_37") (pintype "passive"))
      (node (ref "IC305") (pin "39") (pinfunction "GND_PAD_39") (pintype "passive"))
      (node (ref "IC305") (pin "6") (pinfunction "GPIO1_6") (pintype "passive"))
      (node (ref "IC305") (pin "7") (pinfunction "GPIO2_7") (pintype "passive"))
    )
    (net (code "80") (name "VPWR") (class "Default")
      (node (ref "C327") (pin "1") (pinfunction "1_1") (pintype "passive"))
      (node (ref "C328") (pin "1") (pinfunction "1_1") (pintype "passive"))
      (node (ref "C329") (pin "1") (pinfunction "1_1") (pintype "passive"))
      (node (ref "C330") (pin "1") (pinfunction "1_1") (pintype "passive"))
      (node (ref "C331") (pin "1") (pinfunction "1_1") (pintype "passive"))
      (node (ref "C336") (pin "1") (pinfunction "1_1") (pintype "passive"))
      (node (ref "C337") (pin "1") (pinfunction "1_1") (pintype "passive"))
      (node (ref "C338") (pin "1") (pinfunction "1_1") (pintype "passive"))
      (node (ref "C339") (pin "1") (pinfunction "1_1") (pintype "passive"))
      (node (ref "C340") (pin "1") (pinfunction "1_1") (pintype "passive"))
      (node (ref "C349") (pin "1") (pinfunction "1_1") (pintype "passive"))
      (node (ref "C350") (pin "1") (pinfunction "1_1") (pintype "passive"))
      (node (ref "C351") (pin "1") (pinfunction "1_1") (pintype "passive"))
      (node (ref "C352") (pin "1") (pinfunction "1_1") (pintype "passive"))
      (node (ref "C353") (pin "1") (pinfunction "1_1") (pintype "passive"))
      (node (ref "C360") (pin "1") (pinfunction "1_1") (pintype "passive"))
      (node (ref "C361") (pin "1") (pinfunction "1_1") (pintype "passive"))
      (node (ref "C362") (pin "1") (pinfunction "1_1") (pintype "passive"))
      (node (ref "C363") (pin "1") (pinfunction "1_1") (pintype "passive"))
      (node (ref "C364") (pin "1") (pinfunction "1_1") (pintype "passive"))
      (node (ref "IC302") (pin "23") (pinfunction "VBUS_IN_23") (pintype "passive"))
      (node (ref "IC302") (pin "24") (pinfunction "VBUS_IN_24") (pintype "passive"))
      (node (ref "IC302") (pin "25") (pinfunction "VBUS_IN_25") (pintype "passive"))
      (node (ref "IC303") (pin "23") (pinfunction "VBUS_IN_23") (pintype "passive"))
      (node (ref "IC303") (pin "24") (pinfunction "VBUS_IN_24") (pintype "passive"))
      (node (ref "IC303") (pin "25") (pinfunction "VBUS_IN_25") (pintype "passive"))
      (node (ref "IC304") (pin "23") (pinfunction "VBUS_IN_23") (pintype "passive"))
      (node (ref "IC304") (pin "24") (pinfunction "VBUS_IN_24") (pintype "passive"))
      (node (ref "IC304") (pin "25") (pinfunction "VBUS_IN_25") (pintype "passive"))
      (node (ref "IC305") (pin "23") (pinfunction "VBUS_IN_23") (pintype "passive"))
      (node (ref "IC305") (pin "24") (pinfunction "VBUS_IN_24") (pintype "passive"))
      (node (ref "IC305") (pin "25") (pinfunction "VBUS_IN_25") (pintype "passive"))
    )
    (net (code "81") (name "unconnected-(IC302-ADCIN1-Pad2)") (class "Default")
      (node (ref "IC302") (pin "2") (pinfunction "ADCIN1_2") (pintype "passive"))
    )
    (net (code "82") (name "unconnected-(IC302-ADCIN2-Pad3)") (class "Default")
      (node (ref "IC302") (pin "3") (pinfunction "ADCIN2_3") (pintype "passive"))
    )
    (net (code "83") (name "unconnected-(IC302-I2Cm_IRQ-Pad18)") (class "Default")
      (node (ref "IC302") (pin "18") (pinfunction "I2Cm_IRQ_18") (pintype "passive"))
    )
    (net (code "84") (name "unconnected-(IC302-I2Cm_SCL-Pad17)") (class "Default")
      (node (ref "IC302") (pin "17") (pinfunction "I2Cm_SCL_17") (pintype "passive"))
    )
    (net (code "85") (name "unconnected-(IC302-I2Cm_SDA-Pad16)") (class "Default")
      (node (ref "IC302") (pin "16") (pinfunction "I2Cm_SDA_16") (pintype "passive"))
    )
    (net (code "86") (name "unconnected-(IC302-VBUS-Pad32)") (class "Default")
      (node (ref "IC302") (pin "32") (pinfunction "VBUS_32") (pintype "passive"))
    )
    (net (code "87") (name "unconnected-(IC302-VBUS-Pad33)") (class "Default")
      (node (ref "IC302") (pin "33") (pinfunction "VBUS_33") (pintype "passive"))
    )
    (net (code "88") (name "unconnected-(IC303-ADCIN1-Pad2)") (class "Default")
      (node (ref "IC303") (pin "2") (pinfunction "ADCIN1_2") (pintype "passive"))
    )
    (net (code "89") (name "unconnected-(IC303-ADCIN2-Pad3)") (class "Default")
      (node (ref "IC303") (pin "3") (pinfunction "ADCIN2_3") (pintype "passive"))
    )
    (net (code "90") (name "unconnected-(IC303-I2Cm_IRQ-Pad18)") (class "Default")
      (node (ref "IC303") (pin "18") (pinfunction "I2Cm_IRQ_18") (pintype "passive"))
    )
    (net (code "91") (name "unconnected-(IC303-I2Cm_SCL-Pad17)") (class "Default")
      (node (ref "IC303") (pin "17") (pinfunction "I2Cm_SCL_17") (pintype "passive"))
    )
    (net (code "92") (name "unconnected-(IC303-I2Cm_SDA-Pad16)") (class "Default")
      (node (ref "IC303") (pin "16") (pinfunction "I2Cm_SDA_16") (pintype "passive"))
    )
    (net (code "93") (name "unconnected-(IC303-VBUS-Pad32)") (class "Default")
      (node (ref "IC303") (pin "32") (pinfunction "VBUS_32") (pintype "passive"))
    )
    (net (code "94") (name "unconnected-(IC303-VBUS-Pad33)") (class "Default")
      (node (ref "IC303") (pin "33") (pinfunction "VBUS_33") (pintype "passive"))
    )
    (net (code "95") (name "unconnected-(IC304-ADCIN1-Pad2)") (class "Default")
      (node (ref "IC304") (pin "2") (pinfunction "ADCIN1_2") (pintype "passive"))
    )
    (net (code "96") (name "unconnected-(IC304-ADCIN2-Pad3)") (class "Default")
      (node (ref "IC304") (pin "3") (pinfunction "ADCIN2_3") (pintype "passive"))
    )
    (net (code "97") (name "unconnected-(IC304-I2Cm_IRQ-Pad18)") (class "Default")
      (node (ref "IC304") (pin "18") (pinfunction "I2Cm_IRQ_18") (pintype "passive"))
    )
    (net (code "98") (name "unconnected-(IC304-I2Cm_SCL-Pad17)") (class "Default")
      (node (ref "IC304") (pin "17") (pinfunction "I2Cm_SCL_17") (pintype "passive"))
    )
    (net (code "99") (name "unconnected-(IC304-I2Cm_SDA-Pad16)") (class "Default")
      (node (ref "IC304") (pin "16") (pinfunction "I2Cm_SDA_16") (pintype "passive"))
    )
    (net (code "100") (name "unconnected-(IC304-VBUS-Pad32)") (class "Default")
      (node (ref "IC304") (pin "32") (pinfunction "VBUS_32") (pintype "passive"))
    )
    (net (code "101") (name "unconnected-(IC304-VBUS-Pad33)") (class "Default")
      (node (ref "IC304") (pin "33") (pinfunction "VBUS_33") (pintype "passive"))
    )
    (net (code "102") (name "unconnected-(IC305-ADCIN1-Pad2)") (class "Default")
      (node (ref "IC305") (pin "2") (pinfunction "ADCIN1_2") (pintype "passive"))
    )
    (net (code "103") (name "unconnected-(IC305-ADCIN2-Pad3)") (class "Default")
      (node (ref "IC305") (pin "3") (pinfunction "ADCIN2_3") (pintype "passive"))
    )
    (net (code "104") (name "unconnected-(IC305-I2Cm_IRQ-Pad18)") (class "Default")
      (node (ref "IC305") (pin "18") (pinfunction "I2Cm_IRQ_18") (pintype "passive"))
    )
    (net (code "105") (name "unconnected-(IC305-I2Cm_SCL-Pad17)") (class "Default")
      (node (ref "IC305") (pin "17") (pinfunction "I2Cm_SCL_17") (pintype "passive"))
    )
    (net (code "106") (name "unconnected-(IC305-I2Cm_SDA-Pad16)") (class "Default")
      (node (ref "IC305") (pin "16") (pinfunction "I2Cm_SDA_16") (pintype "passive"))
    )
    (net (code "107") (name "unconnected-(IC305-VBUS-Pad32)") (class "Default")
      (node (ref "IC305") (pin "32") (pinfunction "VBUS_32") (pintype "passive"))
    )
    (net (code "108") (name "unconnected-(IC305-VBUS-Pad33)") (class "Default")
      (node (ref "IC305") (pin "33") (pinfunction "VBUS_33") (pintype "passive"))
    )
  )
)
